# RK3562-VCCIO1.net
KiCad netlist of a schematic drawn in Altium Designer
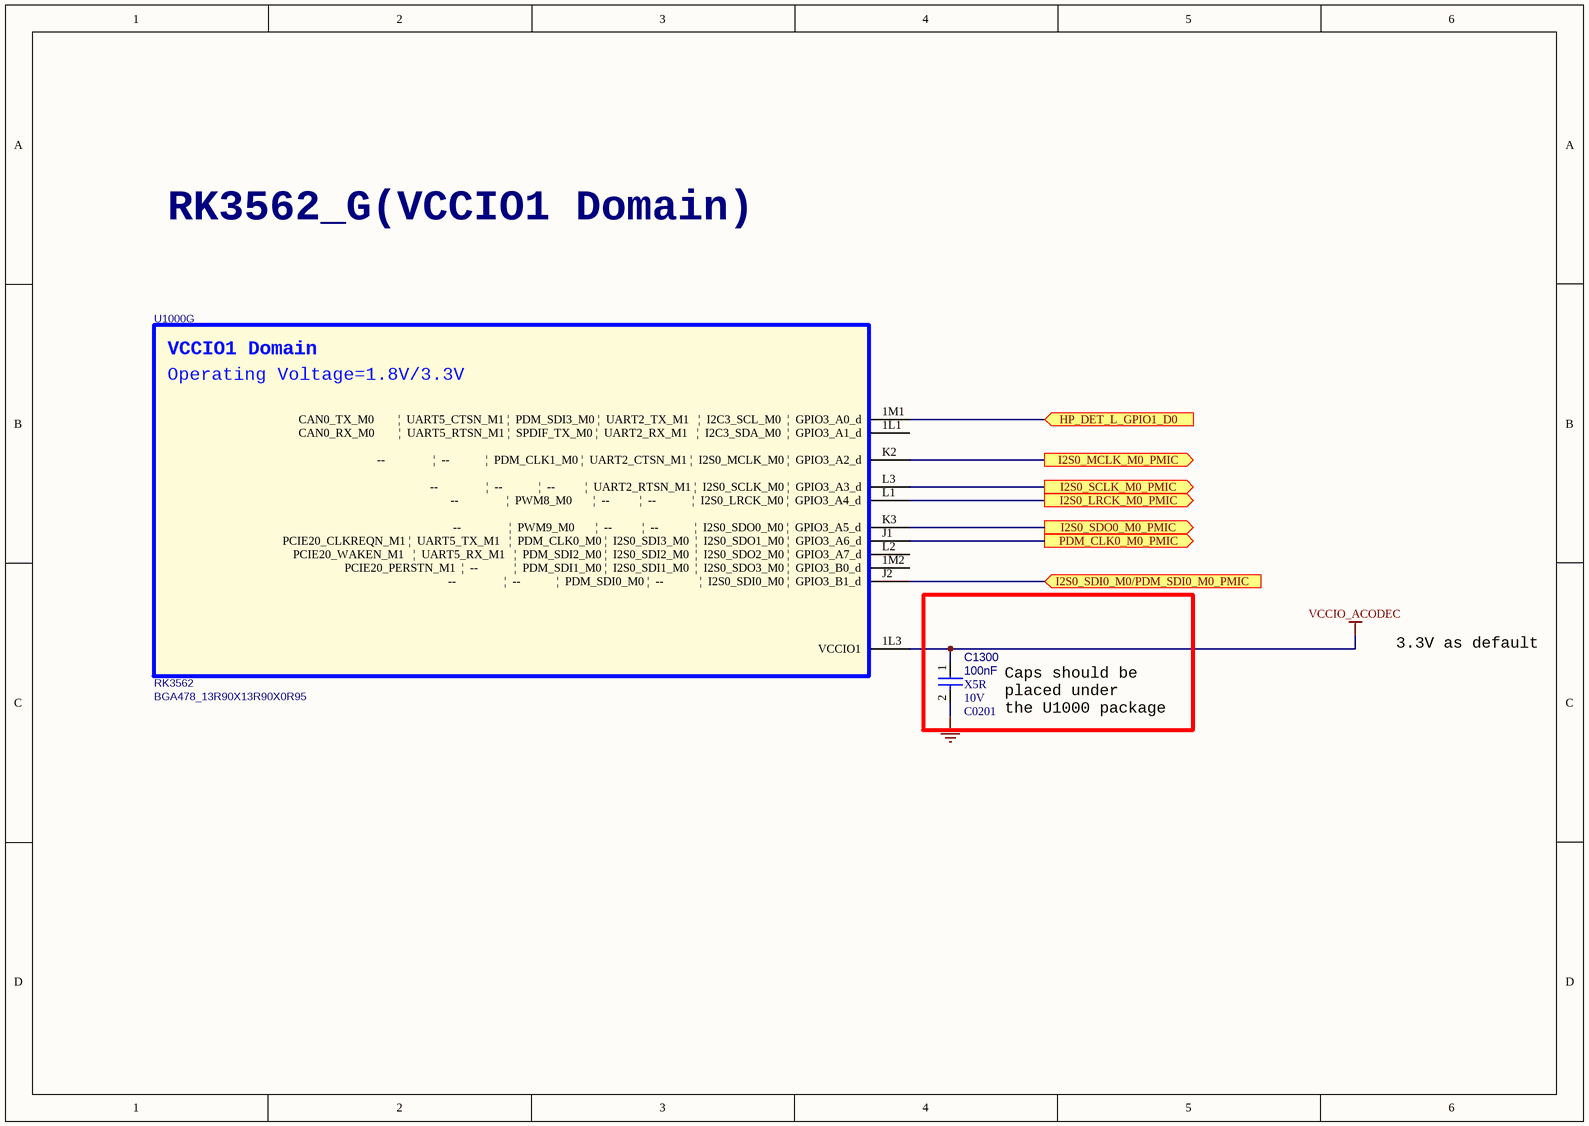
[diagram p0: RK3562-VCCIO1.SchDoc]

(export (version "E")
  (design (tool "Eeschema 10.0.6"))
  (components
    (comp (ref "C1300")
      (value "100nF")
      (footprint "C0201")
      (description "cap,100.00nF,+/-10%,10V,X5R,C0201")
      (fields
        (field (name "DIELECTRIC") "X5R")
        (field (name "PCB FOOTPRINT") "C0201")
        (field (name "VOLTAGE") "10V")
        (field (name "TOLERANCE") "10%")
        (field (name "MANUFACTURER") "TDK")
        (field (name "CREATED BY") "JJJ")
      )
      (libsource (lib "RK3562_REF") (part "CAP NP"))
    )
    (comp (ref "U1000")
      (value "RK3562")
      (footprint "BGA478_13R90X13R90X0R95")
      (description "ROCKCHIP SOC")
      (fields
        (field (name "PCB FOOTPRINT") "BGA478_13R90X13R90X0R95")
        (field (name "MANUFACTURER") "Rockchip (瑞芯微)")
        (field (name "CREATED BY") "JJJ")
      )
      (libsource (lib "RK3562_REF") (part "SOC_RK3562"))
    )
  )
  (nets
    (net (code "1") (name "/HP_DET_L_GPIO1_D0") (class "Default")
      (node (ref "U1000") (pin "1M1") (pinfunction "CAN0_TX_M0________¦__UART5_CTSN_M1_¦__PDM_SDI3_M0_¦__UART2_TX_M1___¦__I2C3_SCL_M0__¦__GPIO3_A0_d_1M1") (pintype "passive"))
    )
    (net (code "2") (name "/I2S0_LRCK_M0_PMIC") (class "Default")
      (node (ref "U1000") (pin "L1") (pinfunction "--________________¦__PWM8_M0_______¦__--__________¦__--____________¦__I2S0_LRCK_M0_¦__GPIO3_A4_d_L1") (pintype "passive"))
    )
    (net (code "3") (name "/I2S0_MCLK_M0_PMIC") (class "Default")
      (node (ref "U1000") (pin "K2") (pinfunction "--________________¦__--____________¦__PDM_CLK1_M0_¦__UART2_CTSN_M1_¦__I2S0_MCLK_M0_¦__GPIO3_A2_d_K2") (pintype "passive"))
    )
    (net (code "4") (name "/I2S0_SCLK_M0_PMIC") (class "Default")
      (node (ref "U1000") (pin "L3") (pinfunction "--________________¦__--____________¦__--__________¦__UART2_RTSN_M1_¦__I2S0_SCLK_M0_¦__GPIO3_A3_d_L3") (pintype "passive"))
    )
    (net (code "5") (name "/I2S0_SDI0_M0{slash}PDM_SDI0_M0_PMIC") (class "Default")
      (node (ref "U1000") (pin "J2") (pinfunction "--________________¦__--____________¦__PDM_SDI0_M0_¦__--____________¦__I2S0_SDI0_M0_¦__GPIO3_B1_d_J2") (pintype "passive"))
    )
    (net (code "6") (name "/I2S0_SDO0_M0_PMIC") (class "Default")
      (node (ref "U1000") (pin "K3") (pinfunction "--________________¦__PWM9_M0_______¦__--__________¦__--____________¦__I2S0_SDO0_M0_¦__GPIO3_A5_d_K3") (pintype "passive"))
    )
    (net (code "7") (name "/PDM_CLK0_M0_PMIC") (class "Default")
      (node (ref "U1000") (pin "J1") (pinfunction "PCIE20_CLKREQN_M1_¦__UART5_TX_M1___¦__PDM_CLK0_M0_¦__I2S0_SDI3_M0__¦__I2S0_SDO1_M0_¦__GPIO3_A6_d_J1") (pintype "passive"))
    )
    (net (code "8") (name "GND") (class "Default")
      (node (ref "C1300") (pin "2") (pinfunction "2_2") (pintype "passive"))
    )
    (net (code "9") (name "VCCIO_ACODEC") (class "Default")
      (node (ref "C1300") (pin "1") (pinfunction "1_1") (pintype "passive"))
      (node (ref "U1000") (pin "1L3") (pinfunction "VCCIO1_1L3") (pintype "passive"))
    )
    (net (code "10") (name "unconnected-(U1000G-CAN0_RX_M0________¦__UART5_RTSN_M1_¦__SPDIF_TX_M0_¦__UART2_RX_M1___¦__I2C3_SDA_M0__¦__GPIO3_A1_d-Pad1L1)") (class "Default")
      (node (ref "U1000") (pin "1L1") (pinfunction "CAN0_RX_M0________¦__UART5_RTSN_M1_¦__SPDIF_TX_M0_¦__UART2_RX_M1___¦__I2C3_SDA_M0__¦__GPIO3_A1_d_1L1") (pintype "passive"))
    )
    (net (code "11") (name "unconnected-(U1000G-PCIE20_PERSTN_M1__¦__--____________¦__PDM_SDI1_M0_¦__I2S0_SDI1_M0__¦__I2S0_SDO3_M0_¦__GPIO3_B0_d-Pad1M2)") (class "Default")
      (node (ref "U1000") (pin "1M2") (pinfunction "PCIE20_PERSTN_M1__¦__--____________¦__PDM_SDI1_M0_¦__I2S0_SDI1_M0__¦__I2S0_SDO3_M0_¦__GPIO3_B0_d_1M2") (pintype "passive"))
    )
    (net (code "12") (name "unconnected-(U1000G-PCIE20_WAKEN_M1___¦__UART5_RX_M1___¦__PDM_SDI2_M0_¦__I2S0_SDI2_M0__¦__I2S0_SDO2_M0_¦__GPIO3_A7_d-PadL2)") (class "Default")
      (node (ref "U1000") (pin "L2") (pinfunction "PCIE20_WAKEN_M1___¦__UART5_RX_M1___¦__PDM_SDI2_M0_¦__I2S0_SDI2_M0__¦__I2S0_SDO2_M0_¦__GPIO3_A7_d_L2") (pintype "passive"))
    )
  )
)
